# WiFi.net
KiCad netlist of a schematic drawn in Altium Designer
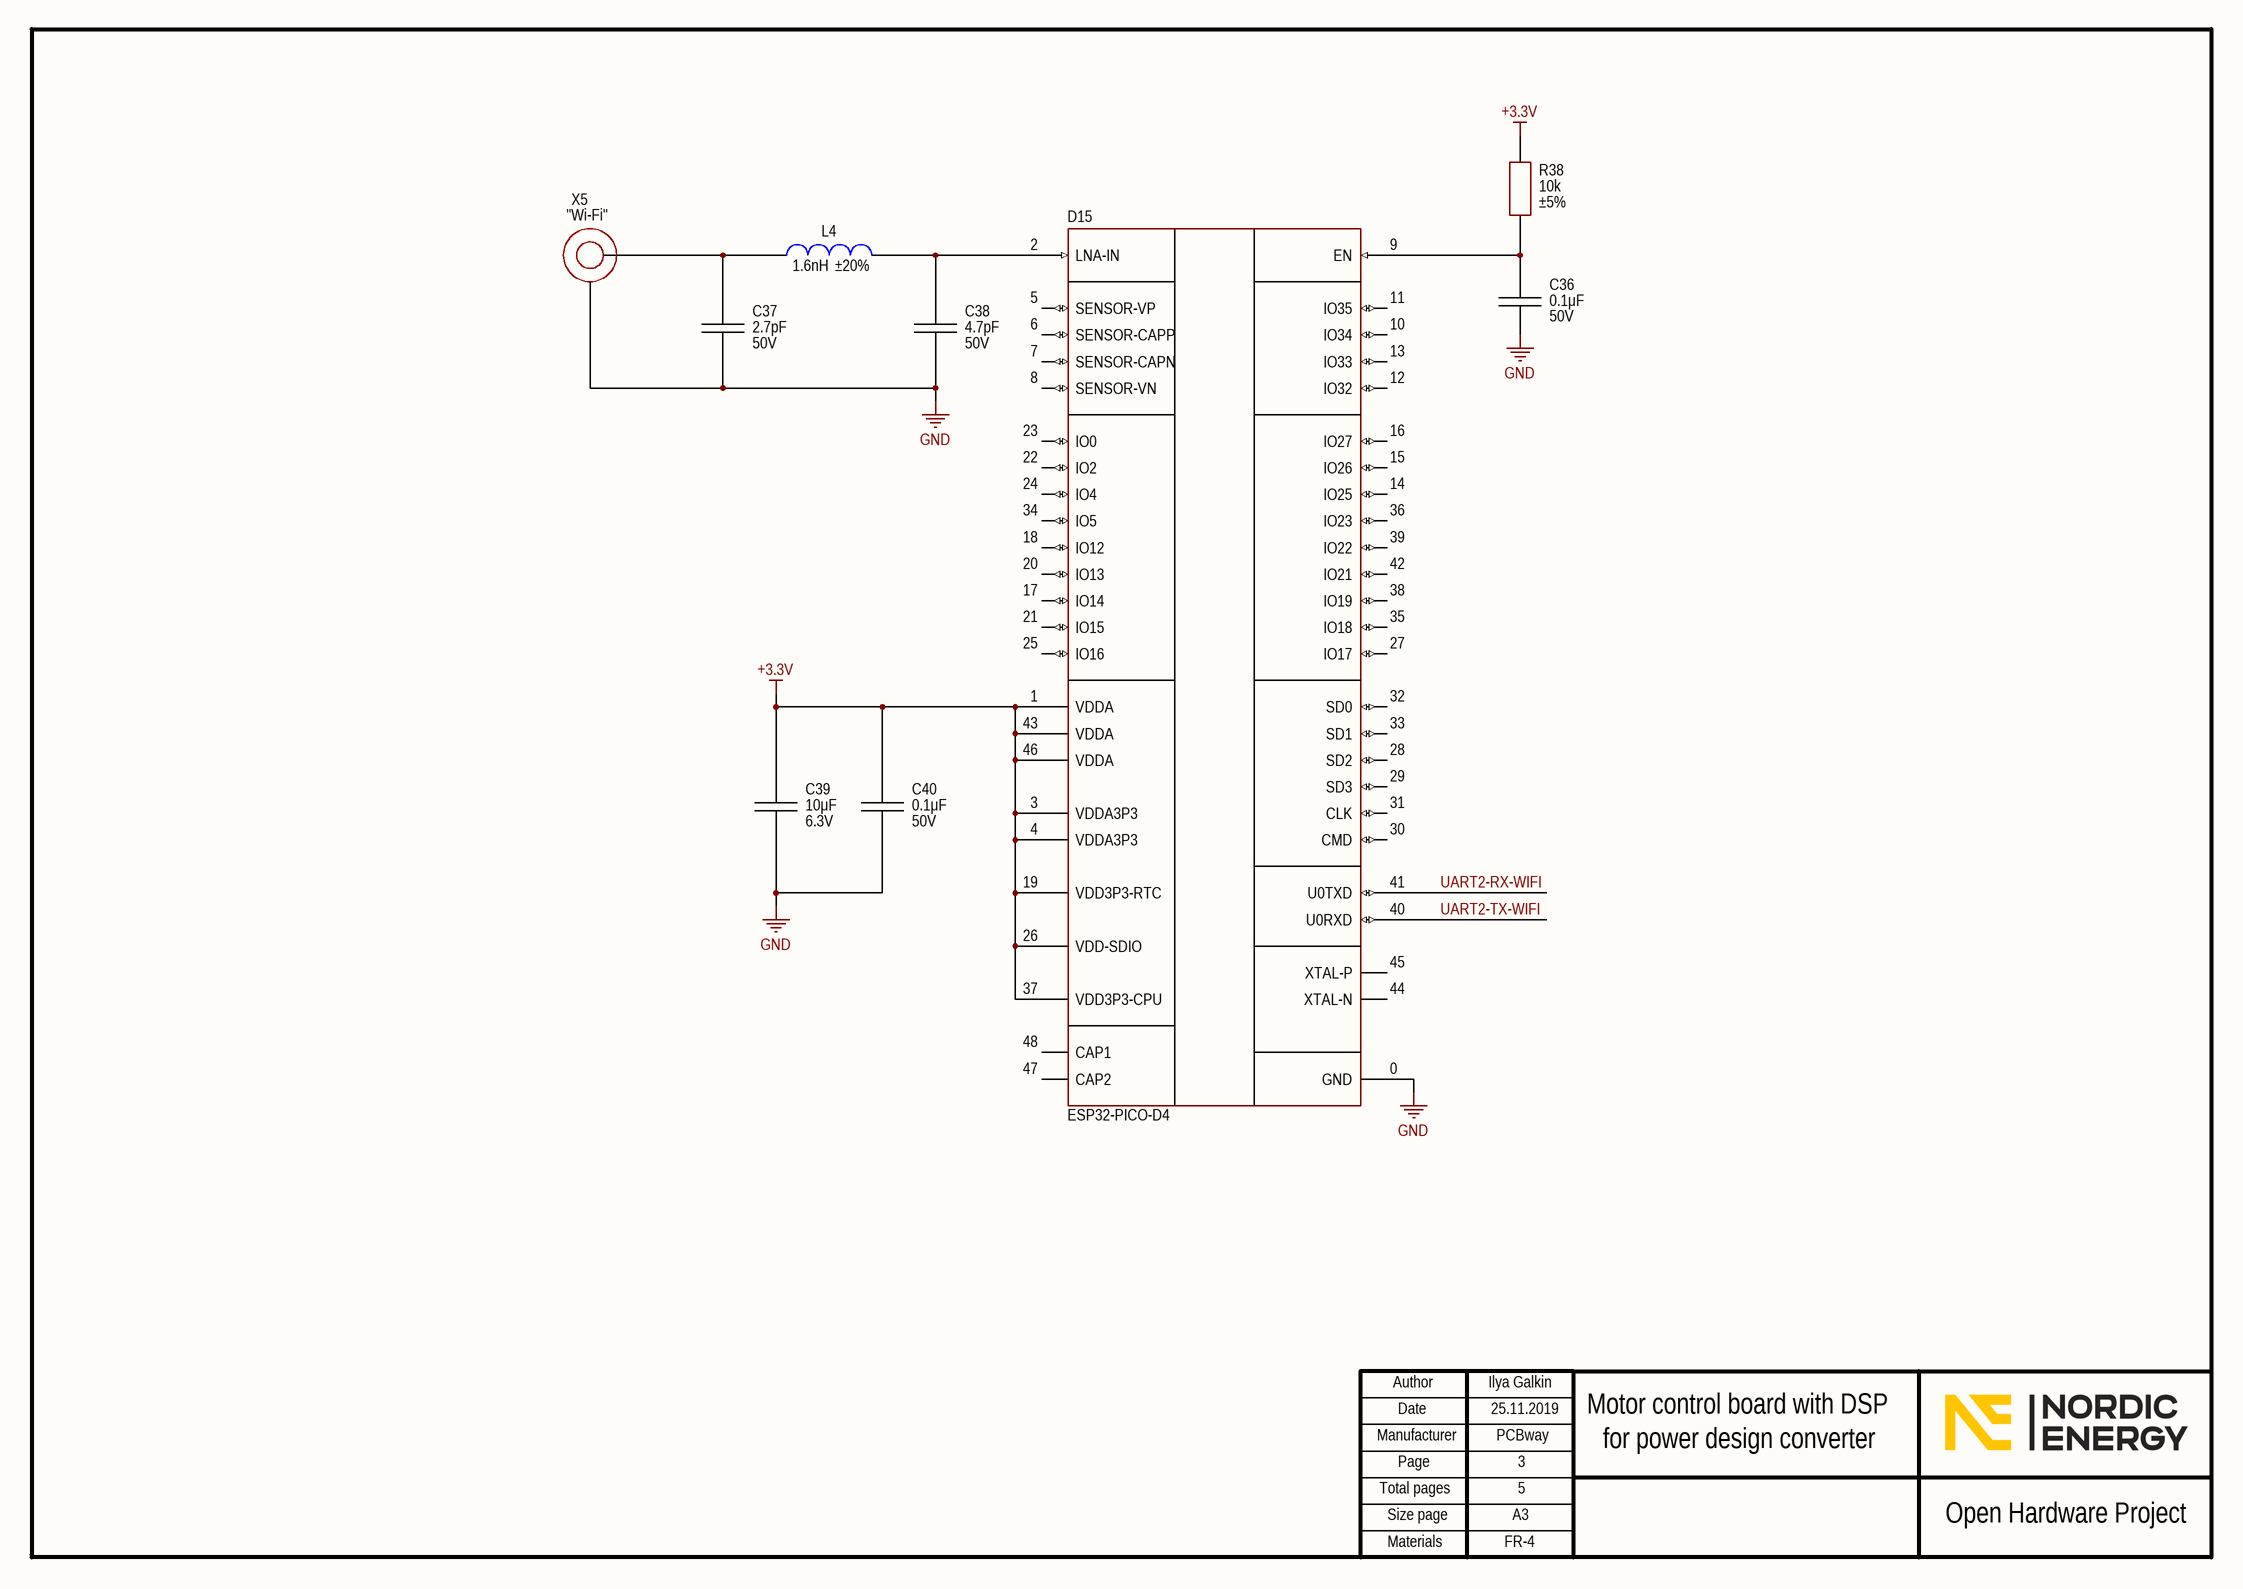
[diagram p0: WiFi.SchDoc]

(export (version "E")
  (design (tool "Eeschema 10.0.6"))
  (components
    (comp (ref "C36")
      (value "0.1μF")
      (footprint "CAP: 0603")
      (fields
        (field (name "MANUFACTURER") "Samsung")
        (field (name "PARTNUMBER") "CL10B104KB8NNNC")
        (field (name "VALUEMANUFACTURERPARTNUMBER") "Ceramic capacitor, 0.1μF, X7R, ±10%, 50V, 0603, -55...+125°C")
        (field (name "VOLTAGE") "50V")
      )
      (libsource (lib "Capacitor") (part "Ceramic_0603"))
    )
    (comp (ref "C37")
      (value "2.7pF")
      (footprint "CAP: 0603")
      (fields
        (field (name "MANUFACTURER") "Samsung")
        (field (name "PARTNUMBER") "CL10C2R7BB8NNNC")
        (field (name "VALUEMANUFACTURERPARTNUMBER") "Ceramic capacitor, 2.7pF, NPO, ±10%, 50V, 0603, -55...+125°C")
        (field (name "VOLTAGE") "50V")
      )
      (libsource (lib "Capacitor") (part "Ceramic_0603"))
    )
    (comp (ref "C38")
      (value "4.7pF")
      (footprint "CAP: 0603")
      (fields
        (field (name "MANUFACTURER") "Samsung")
        (field (name "PARTNUMBER") "CL10C4R7CB8NNNC")
        (field (name "VALUEMANUFACTURERPARTNUMBER") "Ceramic capacitor, 4.7pF, NPO, ±10%, 50V, 0603, -55...+125°C")
        (field (name "VOLTAGE") "50V")
      )
      (libsource (lib "Capacitor") (part "Ceramic_0603"))
    )
    (comp (ref "C39")
      (value "10μF")
      (footprint "CAP: 0603")
      (fields
        (field (name "MANUFACTURER") "Samsung")
        (field (name "PARTNUMBER") "CL10B106MQ8NRNC")
        (field (name "VALUEMANUFACTURERPARTNUMBER") "Ceramic capacitor, 10μF, X7R, ±10%, 6.3V, 0603, -55...+125°C")
        (field (name "VOLTAGE") "6.3V")
      )
      (libsource (lib "Capacitor") (part "Ceramic_0603"))
    )
    (comp (ref "C40")
      (value "0.1μF")
      (footprint "CAP: 0603")
      (fields
        (field (name "MANUFACTURER") "Samsung")
        (field (name "PARTNUMBER") "CL10B104KB8NNNC")
        (field (name "VALUEMANUFACTURERPARTNUMBER") "Ceramic capacitor, 0.1μF, X7R, ±10%, 50V, 0603, -55...+125°C")
        (field (name "VOLTAGE") "50V")
      )
      (libsource (lib "Capacitor") (part "Ceramic_0603"))
    )
    (comp (ref "D15")
      (value "~")
      (footprint "48-LGA (7x7)")
      (description "Wi-Fi+BT")
      (fields (field (name "MANUFACTURER") "Espressif Systems") (field (name "PARTNUMBER") "ESP32-PICO-D4"))
      (libsource (lib "IC. RF transceiver") (part "ESP32-PICO-D4"))
    )
    (comp (ref "L4")
      (value "1.6nH")
      (footprint "IND: 0603")
      (fields
        (field (name "MANUFACTURER") "Bourns")
        (field (name "PARTNUMBER") "CW161009A-1N6D")
        (field (name "VALUEMANUFACTURERPARTNUMBER") "Fixed inductor, 1.6nH, ±20%, 0603, 700mA, -40...+125°C")
        (field (name "TOLERANCE") "±20%")
      )
      (libsource (lib "Inductor") (part "Inductor_0603"))
    )
    (comp (ref "R38")
      (value "10k")
      (footprint "RES: 0603")
      (fields
        (field (name "MANUFACTURER") "Yageo")
        (field (name "PARTNUMBER") "RC0603JR-0710KL")
        (field (name "VALUEMANUFACTURERPARTNUMBER") "Resistor film, 10k, ±5%, 0603, 0.1W, -55...+125°C")
        (field (name "TOLERANCE") "±5%")
      )
      (libsource (lib "Resistor") (part "Resistor_0603"))
    )
    (comp (ref "X5")
      (value "~")
      (footprint "CON: u.Fl")
      (fields
        (field (name "MANUFACTURER") "Hirose Electric")
        (field (name "VALUEMANUFACTURERPARTNUMBER") "Connector u.FL, 50 Ohm, 6GHz")
        (field (name "PARTNUMBER") "U.FL-R-SMT(01)")
        (field (name "COMMENTTEXT") "\"Wi-Fi\"")
      )
      (libsource (lib "Connector") (part "Connector_uFL"))
    )
  )
  (nets
    (net (code "1") (name "+3.3V") (class "Default")
      (node (ref "C39") (pin "2") (pinfunction "2_2") (pintype "power_in"))
      (node (ref "C40") (pin "2") (pinfunction "2_2") (pintype "power_in"))
      (node (ref "D15") (pin "1") (pinfunction "VDDA_1") (pintype "passive"))
      (node (ref "D15") (pin "19") (pinfunction "VDD3P3-RTC_19") (pintype "passive"))
      (node (ref "D15") (pin "26") (pinfunction "VDD-SDIO_26") (pintype "passive"))
      (node (ref "D15") (pin "3") (pinfunction "VDDA3P3_3") (pintype "passive"))
      (node (ref "D15") (pin "37") (pinfunction "VDD3P3-CPU_37") (pintype "passive"))
      (node (ref "D15") (pin "4") (pinfunction "VDDA3P3_4") (pintype "passive"))
      (node (ref "D15") (pin "43") (pinfunction "VDDA_43") (pintype "passive"))
      (node (ref "D15") (pin "46") (pinfunction "VDDA_46") (pintype "passive"))
      (node (ref "R38") (pin "2") (pinfunction "2_2") (pintype "passive"))
    )
    (net (code "2") (name "/UART2-RX-WIFI") (class "Default")
      (node (ref "D15") (pin "41") (pinfunction "U0TXD_41") (pintype "bidirectional"))
    )
    (net (code "3") (name "/UART2-TX-WIFI") (class "Default")
      (node (ref "D15") (pin "40") (pinfunction "U0RXD_40") (pintype "bidirectional"))
    )
    (net (code "4") (name "GND") (class "Default")
      (node (ref "C36") (pin "1") (pinfunction "1_1") (pintype "power_in"))
      (node (ref "C37") (pin "1") (pinfunction "1_1") (pintype "power_in"))
      (node (ref "C38") (pin "1") (pinfunction "1_1") (pintype "power_in"))
      (node (ref "C39") (pin "1") (pinfunction "1_1") (pintype "power_in"))
      (node (ref "C40") (pin "1") (pinfunction "1_1") (pintype "power_in"))
      (node (ref "D15") (pin "0") (pinfunction "GND_0") (pintype "passive"))
      (node (ref "X5") (pin "2") (pinfunction "2_2") (pintype "passive"))
    )
    (net (code "5") (name "Net-(C37-Pad2)") (class "Default")
      (node (ref "C37") (pin "2") (pinfunction "2_2") (pintype "power_in"))
      (node (ref "L4") (pin "2") (pinfunction "2_2") (pintype "passive"))
      (node (ref "X5") (pin "1") (pinfunction "1_1") (pintype "passive"))
    )
    (net (code "6") (name "Net-(D15-EN)") (class "Default")
      (node (ref "C36") (pin "2") (pinfunction "2_2") (pintype "power_in"))
      (node (ref "D15") (pin "9") (pinfunction "EN_9") (pintype "input"))
      (node (ref "R38") (pin "1") (pinfunction "1_1") (pintype "passive"))
    )
    (net (code "7") (name "Net-(D15-LNA-IN)") (class "Default")
      (node (ref "C38") (pin "2") (pinfunction "2_2") (pintype "power_in"))
      (node (ref "D15") (pin "2") (pinfunction "LNA-IN_2") (pintype "input"))
      (node (ref "L4") (pin "1") (pinfunction "1_1") (pintype "passive"))
    )
    (net (code "8") (name "unconnected-(D15-CAP1-Pad48)") (class "Default")
      (node (ref "D15") (pin "48") (pinfunction "CAP1_48") (pintype "passive"))
    )
    (net (code "9") (name "unconnected-(D15-CAP2-Pad47)") (class "Default")
      (node (ref "D15") (pin "47") (pinfunction "CAP2_47") (pintype "passive"))
    )
    (net (code "10") (name "unconnected-(D15-CLK-Pad31)") (class "Default")
      (node (ref "D15") (pin "31") (pinfunction "CLK_31") (pintype "bidirectional"))
    )
    (net (code "11") (name "unconnected-(D15-CMD-Pad30)") (class "Default")
      (node (ref "D15") (pin "30") (pinfunction "CMD_30") (pintype "bidirectional"))
    )
    (net (code "12") (name "unconnected-(D15-IO0-Pad23)") (class "Default")
      (node (ref "D15") (pin "23") (pinfunction "IO0_23") (pintype "bidirectional"))
    )
    (net (code "13") (name "unconnected-(D15-IO2-Pad22)") (class "Default")
      (node (ref "D15") (pin "22") (pinfunction "IO2_22") (pintype "bidirectional"))
    )
    (net (code "14") (name "unconnected-(D15-IO4-Pad24)") (class "Default")
      (node (ref "D15") (pin "24") (pinfunction "IO4_24") (pintype "bidirectional"))
    )
    (net (code "15") (name "unconnected-(D15-IO5-Pad34)") (class "Default")
      (node (ref "D15") (pin "34") (pinfunction "IO5_34") (pintype "bidirectional"))
    )
    (net (code "16") (name "unconnected-(D15-IO12-Pad18)") (class "Default")
      (node (ref "D15") (pin "18") (pinfunction "IO12_18") (pintype "bidirectional"))
    )
    (net (code "17") (name "unconnected-(D15-IO13-Pad20)") (class "Default")
      (node (ref "D15") (pin "20") (pinfunction "IO13_20") (pintype "bidirectional"))
    )
    (net (code "18") (name "unconnected-(D15-IO14-Pad17)") (class "Default")
      (node (ref "D15") (pin "17") (pinfunction "IO14_17") (pintype "bidirectional"))
    )
    (net (code "19") (name "unconnected-(D15-IO15-Pad21)") (class "Default")
      (node (ref "D15") (pin "21") (pinfunction "IO15_21") (pintype "bidirectional"))
    )
    (net (code "20") (name "unconnected-(D15-IO16-Pad25)") (class "Default")
      (node (ref "D15") (pin "25") (pinfunction "IO16_25") (pintype "bidirectional"))
    )
    (net (code "21") (name "unconnected-(D15-IO17-Pad27)") (class "Default")
      (node (ref "D15") (pin "27") (pinfunction "IO17_27") (pintype "bidirectional"))
    )
    (net (code "22") (name "unconnected-(D15-IO18-Pad35)") (class "Default")
      (node (ref "D15") (pin "35") (pinfunction "IO18_35") (pintype "bidirectional"))
    )
    (net (code "23") (name "unconnected-(D15-IO19-Pad38)") (class "Default")
      (node (ref "D15") (pin "38") (pinfunction "IO19_38") (pintype "bidirectional"))
    )
    (net (code "24") (name "unconnected-(D15-IO21-Pad42)") (class "Default")
      (node (ref "D15") (pin "42") (pinfunction "IO21_42") (pintype "bidirectional"))
    )
    (net (code "25") (name "unconnected-(D15-IO22-Pad39)") (class "Default")
      (node (ref "D15") (pin "39") (pinfunction "IO22_39") (pintype "bidirectional"))
    )
    (net (code "26") (name "unconnected-(D15-IO23-Pad36)") (class "Default")
      (node (ref "D15") (pin "36") (pinfunction "IO23_36") (pintype "bidirectional"))
    )
    (net (code "27") (name "unconnected-(D15-IO25-Pad14)") (class "Default")
      (node (ref "D15") (pin "14") (pinfunction "IO25_14") (pintype "bidirectional"))
    )
    (net (code "28") (name "unconnected-(D15-IO26-Pad15)") (class "Default")
      (node (ref "D15") (pin "15") (pinfunction "IO26_15") (pintype "bidirectional"))
    )
    (net (code "29") (name "unconnected-(D15-IO27-Pad16)") (class "Default")
      (node (ref "D15") (pin "16") (pinfunction "IO27_16") (pintype "bidirectional"))
    )
    (net (code "30") (name "unconnected-(D15-IO32-Pad12)") (class "Default")
      (node (ref "D15") (pin "12") (pinfunction "IO32_12") (pintype "bidirectional"))
    )
    (net (code "31") (name "unconnected-(D15-IO33-Pad13)") (class "Default")
      (node (ref "D15") (pin "13") (pinfunction "IO33_13") (pintype "bidirectional"))
    )
    (net (code "32") (name "unconnected-(D15-IO34-Pad10)") (class "Default")
      (node (ref "D15") (pin "10") (pinfunction "IO34_10") (pintype "bidirectional"))
    )
    (net (code "33") (name "unconnected-(D15-IO35-Pad11)") (class "Default")
      (node (ref "D15") (pin "11") (pinfunction "IO35_11") (pintype "bidirectional"))
    )
    (net (code "34") (name "unconnected-(D15-SD0-Pad32)") (class "Default")
      (node (ref "D15") (pin "32") (pinfunction "SD0_32") (pintype "bidirectional"))
    )
    (net (code "35") (name "unconnected-(D15-SD1-Pad33)") (class "Default")
      (node (ref "D15") (pin "33") (pinfunction "SD1_33") (pintype "bidirectional"))
    )
    (net (code "36") (name "unconnected-(D15-SD2-Pad28)") (class "Default")
      (node (ref "D15") (pin "28") (pinfunction "SD2_28") (pintype "bidirectional"))
    )
    (net (code "37") (name "unconnected-(D15-SD3-Pad29)") (class "Default")
      (node (ref "D15") (pin "29") (pinfunction "SD3_29") (pintype "bidirectional"))
    )
    (net (code "38") (name "unconnected-(D15-SENSOR-CAPN-Pad7)") (class "Default")
      (node (ref "D15") (pin "7") (pinfunction "SENSOR-CAPN_7") (pintype "bidirectional"))
    )
    (net (code "39") (name "unconnected-(D15-SENSOR-CAPP-Pad6)") (class "Default")
      (node (ref "D15") (pin "6") (pinfunction "SENSOR-CAPP_6") (pintype "bidirectional"))
    )
    (net (code "40") (name "unconnected-(D15-SENSOR-VN-Pad8)") (class "Default")
      (node (ref "D15") (pin "8") (pinfunction "SENSOR-VN_8") (pintype "bidirectional"))
    )
    (net (code "41") (name "unconnected-(D15-SENSOR-VP-Pad5)") (class "Default")
      (node (ref "D15") (pin "5") (pinfunction "SENSOR-VP_5") (pintype "bidirectional"))
    )
    (net (code "42") (name "unconnected-(D15-XTAL-N-Pad44)") (class "Default")
      (node (ref "D15") (pin "44") (pinfunction "XTAL-N_44") (pintype "passive"))
    )
    (net (code "43") (name "unconnected-(D15-XTAL-P-Pad45)") (class "Default")
      (node (ref "D15") (pin "45") (pinfunction "XTAL-P_45") (pintype "passive"))
    )
  )
)
